# powersupplyboardinprogress.net
KiCad netlist of a schematic drawn in EAGLE
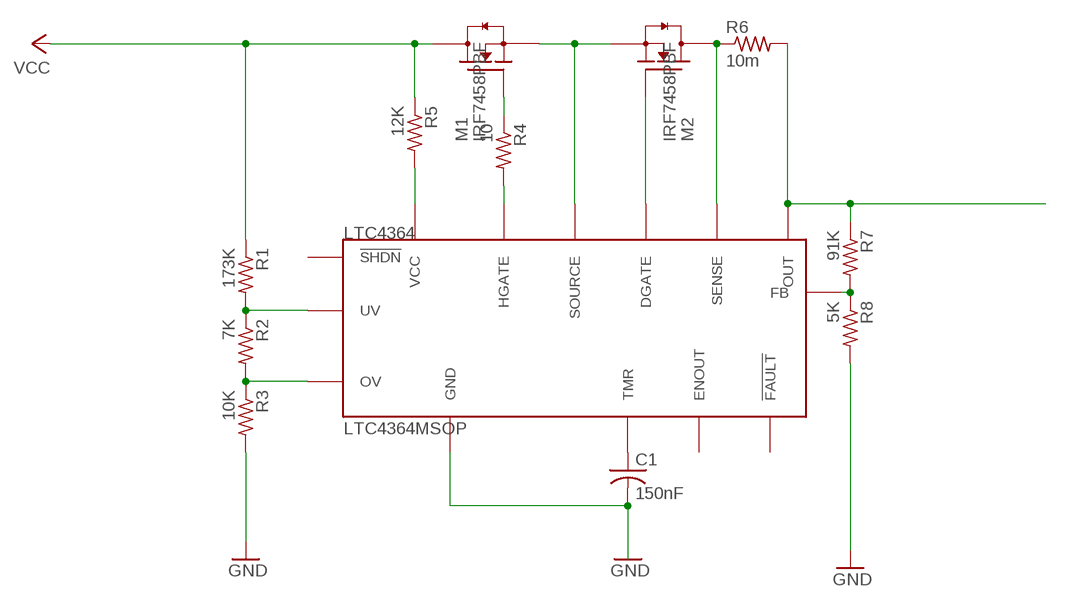
[diagram p0: schematic, sheet 1]

(export (version "E")
  (design (tool "Eeschema 10.0.6"))
  (components
    (comp (ref "C1")
      (value "150nF")
      (footprint "eagle-import:C0805")
      (fields (field (name "SPICEPREFIX") "C"))
      (libsource (lib "eagle-import") (part "C-USC0805"))
    )
    (comp (ref "LTC4364")
      (value "LTC4364MSOP")
      (footprint "eagle-import:MSOP16")
      (fields (field (name "SPICEPREFIX") "X"))
      (libsource (lib "eagle-import") (part "LTC4364MSOP"))
    )
    (comp (ref "M1")
      (value "IRF7458PBF")
      (footprint "eagle-import:SOIC8")
      (fields (field (name "SPICEPREFIX") "M"))
      (libsource (lib "eagle-import") (part "IRF7458PBF"))
    )
    (comp (ref "M2")
      (value "IRF7458PBF")
      (footprint "eagle-import:SOIC8")
      (fields (field (name "SPICEPREFIX") "M"))
      (libsource (lib "eagle-import") (part "IRF7458PBF"))
    )
    (comp (ref "R1")
      (value "173K")
      (footprint "eagle-import:R0805")
      (libsource (lib "eagle-import") (part "R-US_R0805"))
    )
    (comp (ref "R2")
      (value "7K")
      (footprint "eagle-import:R0805")
      (libsource (lib "eagle-import") (part "R-US_R0805"))
    )
    (comp (ref "R3")
      (value "10K")
      (footprint "eagle-import:R0805")
      (libsource (lib "eagle-import") (part "R-US_R0805"))
    )
    (comp (ref "R4")
      (value "10")
      (footprint "eagle-import:R0805")
      (libsource (lib "eagle-import") (part "R-US_R0805"))
    )
    (comp (ref "R5")
      (value "12K")
      (footprint "eagle-import:R0805")
      (libsource (lib "eagle-import") (part "R-US_R0805"))
    )
    (comp (ref "R6")
      (value "10m")
      (footprint "eagle-import:R0805")
      (libsource (lib "eagle-import") (part "R-US_R0805"))
    )
    (comp (ref "R7")
      (value "91K")
      (footprint "eagle-import:R0805")
      (libsource (lib "eagle-import") (part "R-US_R0805"))
    )
    (comp (ref "R8")
      (value "5K")
      (footprint "eagle-import:R0805")
      (libsource (lib "eagle-import") (part "R-US_R0805"))
    )
  )
  (nets
    (net (code "1") (name "GND") (class "Default")
      (node (ref "C1") (pin "2") (pinfunction "2_2") (pintype "passive"))
      (node (ref "LTC4364") (pin "GND") (pinfunction "GND_GND") (pintype "bidirectional"))
      (node (ref "R3") (pin "2") (pinfunction "2_2") (pintype "passive"))
      (node (ref "R8") (pin "2") (pinfunction "2_2") (pintype "passive"))
    )
    (net (code "2") (name "Net-(C1-Pad1)") (class "Default")
      (node (ref "C1") (pin "1") (pinfunction "1_1") (pintype "passive"))
      (node (ref "LTC4364") (pin "TMR") (pinfunction "TMR_TMR") (pintype "bidirectional"))
    )
    (net (code "3") (name "Net-(LTC4364-PadFB)") (class "Default")
      (node (ref "LTC4364") (pin "FB") (pinfunction "FB_FB") (pintype "bidirectional"))
      (node (ref "R7") (pin "2") (pinfunction "2_2") (pintype "passive"))
      (node (ref "R8") (pin "1") (pinfunction "1_1") (pintype "passive"))
    )
    (net (code "4") (name "Net-(LTC4364-PadHGATE)") (class "Default")
      (node (ref "LTC4364") (pin "HGATE") (pinfunction "HGATE_HGATE") (pintype "bidirectional"))
      (node (ref "R4") (pin "2") (pinfunction "2_2") (pintype "passive"))
    )
    (net (code "5") (name "Net-(LTC4364-PadOUT)") (class "Default")
      (node (ref "LTC4364") (pin "OUT") (pinfunction "OUT_OUT") (pintype "bidirectional"))
      (node (ref "R6") (pin "2") (pinfunction "2_2") (pintype "passive"))
      (node (ref "R7") (pin "1") (pinfunction "1_1") (pintype "passive"))
    )
    (net (code "6") (name "Net-(LTC4364-PadOV)") (class "Default")
      (node (ref "LTC4364") (pin "OV") (pinfunction "OV_OV") (pintype "bidirectional"))
      (node (ref "R2") (pin "2") (pinfunction "2_2") (pintype "passive"))
      (node (ref "R3") (pin "1") (pinfunction "1_1") (pintype "passive"))
    )
    (net (code "7") (name "Net-(LTC4364-PadSENSE)") (class "Default")
      (node (ref "LTC4364") (pin "SENSE") (pinfunction "SENSE_SENSE") (pintype "bidirectional"))
      (node (ref "M2") (pin "D1") (pinfunction "D_D1") (pintype "bidirectional"))
      (node (ref "M2") (pin "D2") (pinfunction "D_D2") (pintype "bidirectional"))
      (node (ref "M2") (pin "D3") (pinfunction "D_D3") (pintype "bidirectional"))
      (node (ref "M2") (pin "D4") (pinfunction "D_D4") (pintype "bidirectional"))
      (node (ref "R6") (pin "1") (pinfunction "1_1") (pintype "passive"))
    )
    (net (code "8") (name "Net-(LTC4364-PadSOURCE)") (class "Default")
      (node (ref "LTC4364") (pin "SOURCE") (pinfunction "SOURCE_SOURCE") (pintype "bidirectional"))
      (node (ref "M1") (pin "S1") (pinfunction "S_S1") (pintype "passive"))
      (node (ref "M1") (pin "S2") (pinfunction "S_S2") (pintype "passive"))
      (node (ref "M1") (pin "S3") (pinfunction "S_S3") (pintype "passive"))
      (node (ref "M2") (pin "S1") (pinfunction "S_S1") (pintype "passive"))
      (node (ref "M2") (pin "S2") (pinfunction "S_S2") (pintype "passive"))
      (node (ref "M2") (pin "S3") (pinfunction "S_S3") (pintype "passive"))
    )
    (net (code "9") (name "Net-(LTC4364-PadUV)") (class "Default")
      (node (ref "LTC4364") (pin "UV") (pinfunction "UV_UV") (pintype "bidirectional"))
      (node (ref "R1") (pin "2") (pinfunction "2_2") (pintype "passive"))
      (node (ref "R2") (pin "1") (pinfunction "1_1") (pintype "passive"))
    )
    (net (code "10") (name "Net-(LTC4364-PadVCC)") (class "Default")
      (node (ref "LTC4364") (pin "VCC") (pinfunction "VCC_VCC") (pintype "bidirectional"))
      (node (ref "R5") (pin "2") (pinfunction "2_2") (pintype "passive"))
    )
    (net (code "11") (name "Net-(M1-G)") (class "Default")
      (node (ref "M1") (pin "G1") (pinfunction "G_G1") (pintype "passive"))
      (node (ref "R4") (pin "1") (pinfunction "1_1") (pintype "passive"))
    )
    (net (code "12") (name "Net-(M2-G)") (class "Default")
      (node (ref "LTC4364") (pin "DGATE") (pinfunction "DGATE_DGATE") (pintype "bidirectional"))
      (node (ref "M2") (pin "G1") (pinfunction "G_G1") (pintype "passive"))
    )
    (net (code "13") (name "VCC") (class "Default")
      (node (ref "M1") (pin "D1") (pinfunction "D_D1") (pintype "bidirectional"))
      (node (ref "M1") (pin "D2") (pinfunction "D_D2") (pintype "bidirectional"))
      (node (ref "M1") (pin "D3") (pinfunction "D_D3") (pintype "bidirectional"))
      (node (ref "M1") (pin "D4") (pinfunction "D_D4") (pintype "bidirectional"))
      (node (ref "R1") (pin "1") (pinfunction "1_1") (pintype "passive"))
      (node (ref "R5") (pin "1") (pinfunction "1_1") (pintype "passive"))
    )
    (net (code "14") (name "unconnected-(LTC4364-PadENOUT)") (class "Default")
      (node (ref "LTC4364") (pin "ENOUT") (pinfunction "ENOUT_ENOUT") (pintype "bidirectional"))
    )
    (net (code "15") (name "unconnected-(LTC4364-~{FAULT}-PadFLT)") (class "Default")
      (node (ref "LTC4364") (pin "FLT") (pinfunction "~{FAULT}_FLT") (pintype "bidirectional"))
    )
    (net (code "16") (name "unconnected-(LTC4364-~{SHDN}-PadSHDN)") (class "Default")
      (node (ref "LTC4364") (pin "SHDN") (pinfunction "~{SHDN}_SHDN") (pintype "bidirectional"))
    )
  )
)
